# Sheet_1_2026-10-05.net
KiCad netlist of a schematic drawn in Altium Designer
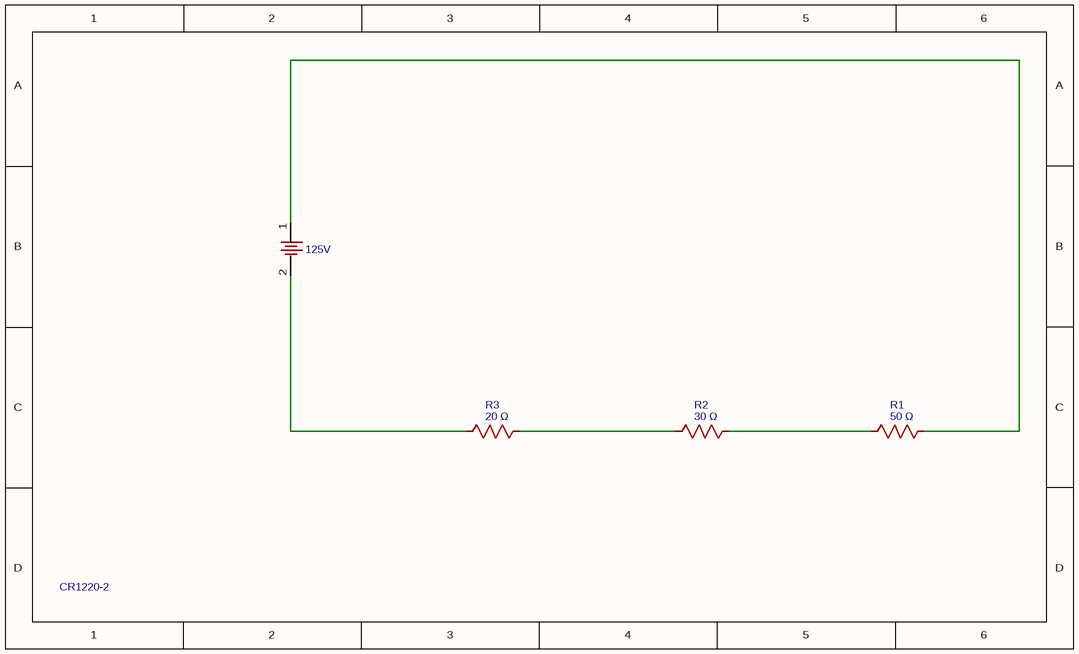
[diagram p0: Sheet_1_2026-10-05.schdoc]

(export (version "E")
  (design (tool "Eeschema 10.0.6"))
  (components
    (comp (ref "125V")
      (value "CR1220-2")
      (fields (field (name "MANUFACTURER") "Q&J"))
      (libsource (lib "altium-import") (part "root_3_CR1220-2_"))
    )
    (comp (ref "R1")
      (value "50 Ω")
      (fields (field (name "CONTRIBUTOR") "LCEDA_Lib"))
      (libsource (lib "altium-import") (part "root_0_50 Ω_"))
    )
    (comp (ref "R2")
      (value "30 Ω")
      (fields (field (name "CONTRIBUTOR") "LCEDA_Lib"))
      (libsource (lib "altium-import") (part "root_0_30 Ω_"))
    )
    (comp (ref "R3")
      (value "20 Ω")
      (fields (field (name "CONTRIBUTOR") "LCEDA_Lib"))
      (libsource (lib "altium-import") (part "root_0_20 Ω_"))
    )
  )
  (nets
    (net (code "1") (name "Net-(125V-Pad1)") (class "Default")
      (node (ref "125V") (pin "1") (pinfunction "1_1") (pintype "passive"))
      (node (ref "R1") (pin "2") (pinfunction "2_2") (pintype "passive"))
    )
    (net (code "2") (name "Net-(125V-Pad2)") (class "Default")
      (node (ref "125V") (pin "2") (pinfunction "2_2") (pintype "passive"))
      (node (ref "R3") (pin "1") (pinfunction "1_1") (pintype "passive"))
    )
    (net (code "3") (name "Net-(R1-Pad1)") (class "Default")
      (node (ref "R1") (pin "1") (pinfunction "1_1") (pintype "passive"))
      (node (ref "R2") (pin "2") (pinfunction "2_2") (pintype "passive"))
    )
    (net (code "4") (name "Net-(R2-Pad1)") (class "Default")
      (node (ref "R2") (pin "1") (pinfunction "1_1") (pintype "passive"))
      (node (ref "R3") (pin "2") (pinfunction "2_2") (pintype "passive"))
    )
  )
)
